# AUGER_CONTROL_BOARD.net
KiCad netlist of a schematic drawn in EAGLE
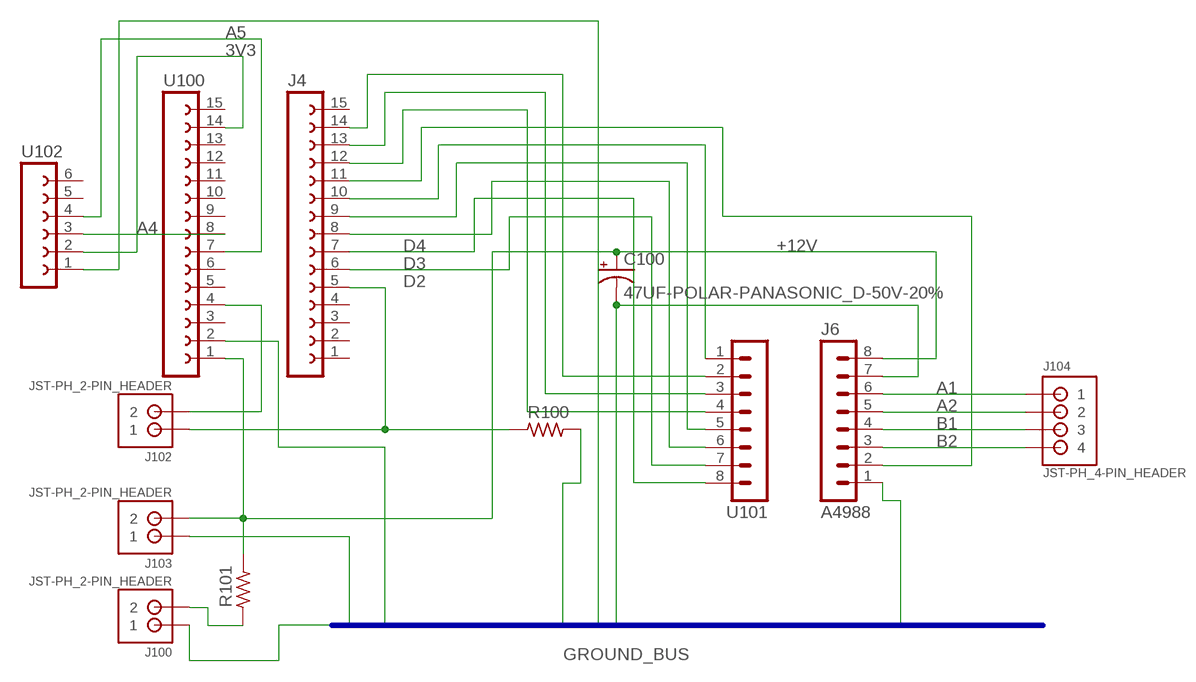
[diagram p0: schematic, sheet 1]

(export (version "E")
  (design (tool "Eeschema 10.0.6"))
  (components
    (comp (ref "C100")
      (value "47UF-POLAR-PANASONIC_D-50V-20%")
      (footprint "eagle-import:PANASONIC_D")
      (libsource (lib "eagle-import") (part "47UF-POLAR-PANASONIC_D-50V-20%"))
    )
    (comp (ref "J4")
      (value "FE15-1")
      (footprint "eagle-import:FE15")
      (libsource (lib "eagle-import") (part "FE15-1"))
    )
    (comp (ref "J6")
      (value "A4988")
      (footprint "eagle-import:MA08-1")
      (libsource (lib "eagle-import") (part "MA08-1"))
    )
    (comp (ref "J100")
      (value "JST-PH_2-PIN_HEADER")
      (footprint "eagle-import:JST_B2B-PH_HEADER")
      (libsource (lib "eagle-import") (part "JST-PH_2-PIN_HEADER"))
    )
    (comp (ref "J102")
      (value "JST-PH_2-PIN_HEADER")
      (footprint "eagle-import:JST_B2B-PH_HEADER")
      (libsource (lib "eagle-import") (part "JST-PH_2-PIN_HEADER"))
    )
    (comp (ref "J103")
      (value "JST-PH_2-PIN_HEADER")
      (footprint "eagle-import:JST_B2B-PH_HEADER")
      (libsource (lib "eagle-import") (part "JST-PH_2-PIN_HEADER"))
    )
    (comp (ref "J104")
      (value "JST-PH_4-PIN_HEADER")
      (footprint "eagle-import:JST_B4B-PH_HEADER")
      (libsource (lib "eagle-import") (part "JST-PH_4-PIN_HEADER"))
    )
    (comp (ref "R100")
      (value "R_5025")
      (footprint "eagle-import:R5025")
      (libsource (lib "eagle-import") (part "R_5025"))
    )
    (comp (ref "R101")
      (value "R_5025")
      (footprint "eagle-import:R5025")
      (libsource (lib "eagle-import") (part "R_5025"))
    )
    (comp (ref "U100")
      (value "FE15-1")
      (footprint "eagle-import:FE15")
      (libsource (lib "eagle-import") (part "FE15-1"))
    )
    (comp (ref "U101")
      (value "MA08-1")
      (footprint "eagle-import:MA08-1")
      (libsource (lib "eagle-import") (part "MA08-1"))
    )
    (comp (ref "U102")
      (value "FE06-1")
      (footprint "eagle-import:FE06")
      (libsource (lib "eagle-import") (part "FE06-1"))
    )
  )
  (nets
    (net (code "1") (name "/+12V") (class "Default")
      (node (ref "C100") (pin "+") (pinfunction "+_+") (pintype "passive"))
      (node (ref "J103") (pin "P2") (pinfunction "2_P2") (pintype "bidirectional"))
      (node (ref "J6") (pin "8") (pinfunction "8_8") (pintype "passive"))
      (node (ref "R101") (pin "2") (pinfunction "2_2") (pintype "passive"))
      (node (ref "U100") (pin "1") (pinfunction "1_1") (pintype "passive"))
    )
    (net (code "2") (name "/3V3") (class "Default")
      (node (ref "U100") (pin "14") (pinfunction "14_14") (pintype "passive"))
      (node (ref "U102") (pin "2") (pinfunction "2_2") (pintype "passive"))
    )
    (net (code "3") (name "/A1") (class "Default")
      (node (ref "J104") (pin "P1") (pinfunction "1_P1") (pintype "bidirectional"))
      (node (ref "J6") (pin "6") (pinfunction "6_6") (pintype "passive"))
    )
    (net (code "4") (name "/A2") (class "Default")
      (node (ref "J104") (pin "P2") (pinfunction "2_P2") (pintype "bidirectional"))
      (node (ref "J6") (pin "5") (pinfunction "5_5") (pintype "passive"))
    )
    (net (code "5") (name "/A4") (class "Default")
      (node (ref "U100") (pin "8") (pinfunction "8_8") (pintype "passive"))
      (node (ref "U102") (pin "3") (pinfunction "3_3") (pintype "passive"))
    )
    (net (code "6") (name "/A5") (class "Default")
      (node (ref "U100") (pin "7") (pinfunction "7_7") (pintype "passive"))
      (node (ref "U102") (pin "4") (pinfunction "4_4") (pintype "passive"))
    )
    (net (code "7") (name "/B1") (class "Default")
      (node (ref "J104") (pin "P3") (pinfunction "3_P3") (pintype "bidirectional"))
      (node (ref "J6") (pin "4") (pinfunction "4_4") (pintype "passive"))
    )
    (net (code "8") (name "/B2") (class "Default")
      (node (ref "J104") (pin "P4") (pinfunction "4_P4") (pintype "bidirectional"))
      (node (ref "J6") (pin "3") (pinfunction "3_3") (pintype "passive"))
    )
    (net (code "9") (name "/D2") (class "Default")
      (node (ref "J102") (pin "P1") (pinfunction "1_P1") (pintype "bidirectional"))
      (node (ref "J4") (pin "5") (pinfunction "5_5") (pintype "passive"))
      (node (ref "R100") (pin "1") (pinfunction "1_1") (pintype "passive"))
    )
    (net (code "10") (name "/D3") (class "Default")
      (node (ref "J4") (pin "6") (pinfunction "6_6") (pintype "passive"))
      (node (ref "U101") (pin "7") (pinfunction "7_7") (pintype "passive"))
    )
    (net (code "11") (name "/D4") (class "Default")
      (node (ref "J4") (pin "7") (pinfunction "7_7") (pintype "passive"))
      (node (ref "U101") (pin "8") (pinfunction "8_8") (pintype "passive"))
    )
    (net (code "12") (name "/GROUND_BUS") (class "Default")
      (node (ref "C100") (pin "-") (pinfunction "-_-") (pintype "passive"))
      (node (ref "J100") (pin "P1") (pinfunction "1_P1") (pintype "bidirectional"))
      (node (ref "J103") (pin "P1") (pinfunction "1_P1") (pintype "bidirectional"))
      (node (ref "J6") (pin "1") (pinfunction "1_1") (pintype "passive"))
      (node (ref "J6") (pin "7") (pinfunction "7_7") (pintype "passive"))
      (node (ref "R100") (pin "2") (pinfunction "2_2") (pintype "passive"))
      (node (ref "U100") (pin "2") (pinfunction "2_2") (pintype "passive"))
      (node (ref "U102") (pin "1") (pinfunction "1_1") (pintype "passive"))
    )
    (net (code "14") (name "Net-(J4-Pad8)") (class "Default")
      (node (ref "J4") (pin "8") (pinfunction "8_8") (pintype "passive"))
      (node (ref "U101") (pin "6") (pinfunction "6_6") (pintype "passive"))
    )
    (net (code "15") (name "Net-(J4-Pad9)") (class "Default")
      (node (ref "J4") (pin "9") (pinfunction "9_9") (pintype "passive"))
      (node (ref "U101") (pin "5") (pinfunction "5_5") (pintype "passive"))
    )
    (net (code "16") (name "Net-(J4-Pad10)") (class "Default")
      (node (ref "J4") (pin "10") (pinfunction "10_10") (pintype "passive"))
      (node (ref "U101") (pin "1") (pinfunction "1_1") (pintype "passive"))
    )
    (net (code "17") (name "Net-(J4-Pad11)") (class "Default")
      (node (ref "J4") (pin "11") (pinfunction "11_11") (pintype "passive"))
      (node (ref "J6") (pin "2") (pinfunction "2_2") (pintype "passive"))
    )
    (net (code "18") (name "Net-(J4-Pad12)") (class "Default")
      (node (ref "J4") (pin "12") (pinfunction "12_12") (pintype "passive"))
      (node (ref "U101") (pin "4") (pinfunction "4_4") (pintype "passive"))
    )
    (net (code "19") (name "Net-(J4-Pad13)") (class "Default")
      (node (ref "J4") (pin "13") (pinfunction "13_13") (pintype "passive"))
      (node (ref "U101") (pin "3") (pinfunction "3_3") (pintype "passive"))
    )
    (net (code "20") (name "Net-(J4-Pad14)") (class "Default")
      (node (ref "J4") (pin "14") (pinfunction "14_14") (pintype "passive"))
      (node (ref "U101") (pin "2") (pinfunction "2_2") (pintype "passive"))
    )
    (net (code "21") (name "Net-(J100-2)") (class "Default")
      (node (ref "J100") (pin "P2") (pinfunction "2_P2") (pintype "bidirectional"))
      (node (ref "R101") (pin "1") (pinfunction "1_1") (pintype "passive"))
    )
    (net (code "22") (name "Net-(J102-2)") (class "Default")
      (node (ref "J102") (pin "P2") (pinfunction "2_P2") (pintype "bidirectional"))
      (node (ref "U100") (pin "4") (pinfunction "4_4") (pintype "passive"))
    )
    (net (code "23") (name "unconnected-(J4-Pad1)") (class "Default")
      (node (ref "J4") (pin "1") (pinfunction "1_1") (pintype "passive"))
    )
    (net (code "24") (name "unconnected-(J4-Pad2)") (class "Default")
      (node (ref "J4") (pin "2") (pinfunction "2_2") (pintype "passive"))
    )
    (net (code "25") (name "unconnected-(J4-Pad3)") (class "Default")
      (node (ref "J4") (pin "3") (pinfunction "3_3") (pintype "passive"))
    )
    (net (code "26") (name "unconnected-(J4-Pad4)") (class "Default")
      (node (ref "J4") (pin "4") (pinfunction "4_4") (pintype "passive"))
    )
    (net (code "27") (name "unconnected-(J4-Pad15)") (class "Default")
      (node (ref "J4") (pin "15") (pinfunction "15_15") (pintype "passive"))
    )
    (net (code "28") (name "unconnected-(U100-Pad3)") (class "Default")
      (node (ref "U100") (pin "3") (pinfunction "3_3") (pintype "passive"))
    )
    (net (code "29") (name "unconnected-(U100-Pad5)") (class "Default")
      (node (ref "U100") (pin "5") (pinfunction "5_5") (pintype "passive"))
    )
    (net (code "30") (name "unconnected-(U100-Pad6)") (class "Default")
      (node (ref "U100") (pin "6") (pinfunction "6_6") (pintype "passive"))
    )
    (net (code "31") (name "unconnected-(U100-Pad9)") (class "Default")
      (node (ref "U100") (pin "9") (pinfunction "9_9") (pintype "passive"))
    )
    (net (code "32") (name "unconnected-(U100-Pad10)") (class "Default")
      (node (ref "U100") (pin "10") (pinfunction "10_10") (pintype "passive"))
    )
    (net (code "33") (name "unconnected-(U100-Pad11)") (class "Default")
      (node (ref "U100") (pin "11") (pinfunction "11_11") (pintype "passive"))
    )
    (net (code "34") (name "unconnected-(U100-Pad12)") (class "Default")
      (node (ref "U100") (pin "12") (pinfunction "12_12") (pintype "passive"))
    )
    (net (code "35") (name "unconnected-(U100-Pad13)") (class "Default")
      (node (ref "U100") (pin "13") (pinfunction "13_13") (pintype "passive"))
    )
    (net (code "36") (name "unconnected-(U100-Pad15)") (class "Default")
      (node (ref "U100") (pin "15") (pinfunction "15_15") (pintype "passive"))
    )
    (net (code "37") (name "unconnected-(U102-Pad5)") (class "Default")
      (node (ref "U102") (pin "5") (pinfunction "5_5") (pintype "passive"))
    )
    (net (code "38") (name "unconnected-(U102-Pad6)") (class "Default")
      (node (ref "U102") (pin "6") (pinfunction "6_6") (pintype "passive"))
    )
  )
)
